# 4_SIM.net
KiCad netlist of a schematic drawn in Altium Designer
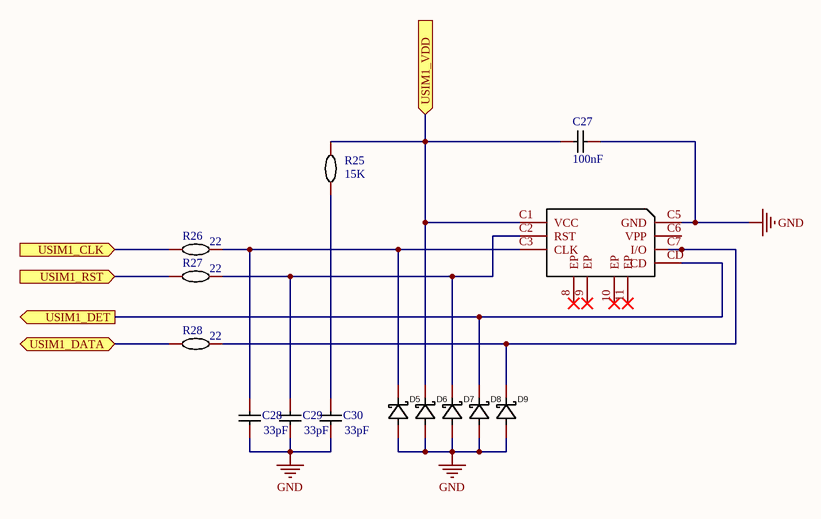
[diagram p0: 4_SIM卡座电路.SchDoc]

(export (version "E")
  (design (tool "Eeschema 10.0.6"))
  (components
    (comp (ref "C27")
      (value "100nF")
      (footprint "0603C")
      (fields (field (name "MANUFACTURER PART") "CL31A106KBHNNNE"))
      (libsource (lib "3_C5157152_TP5000移动电源方案验证板.schdoc") (part "CL31A106KBHNNNE"))
    )
    (comp (ref "C28")
      (value "33pF")
      (footprint "0402C")
      (fields (field (name "MANUFACTURER PART") "CL31A106KBHNNNE"))
      (libsource (lib "3_C5157152_TP5000移动电源方案验证板.schdoc") (part "CL31A106KBHNNNE"))
    )
    (comp (ref "C29")
      (value "33pF")
      (footprint "0402C")
      (fields (field (name "MANUFACTURER PART") "CL31A106KBHNNNE"))
      (libsource (lib "3_C5157152_TP5000移动电源方案验证板.schdoc") (part "CL31A106KBHNNNE"))
    )
    (comp (ref "C30")
      (value "33pF")
      (footprint "0402C")
      (fields (field (name "MANUFACTURER PART") "CL31A106KBHNNNE"))
      (libsource (lib "3_C5157152_TP5000移动电源方案验证板.schdoc") (part "CL31A106KBHNNNE"))
    )
    (comp (ref "CARD1")
      (value "SMN-303")
      (footprint "SIM-SMD_SMN-303")
      (libsource (lib "SIM-3031_SMN-303.schdoc") (part "SMN-303"))
    )
    (comp (ref "D5")
      (value "~")
      (footprint "SOD-123FL_L2.8-W1.8-LS3.7-RD")
      (fields (field (name "MANUFACTURER PART") "SMF75A"))
      (libsource (lib "SMF75A_C51164161_SMF75A_C5116416.schdoc") (part "SMF75A_C5116416"))
    )
    (comp (ref "D6")
      (value "~")
      (footprint "SOD-123FL_L2.8-W1.8-LS3.7-RD")
      (fields (field (name "MANUFACTURER PART") "SMF75A"))
      (libsource (lib "SMF75A_C51164161_SMF75A_C5116416.schdoc") (part "SMF75A_C5116416"))
    )
    (comp (ref "D7")
      (value "~")
      (footprint "SOD-123FL_L2.8-W1.8-LS3.7-RD")
      (fields (field (name "MANUFACTURER PART") "SMF75A"))
      (libsource (lib "SMF75A_C51164161_SMF75A_C5116416.schdoc") (part "SMF75A_C5116416"))
    )
    (comp (ref "D8")
      (value "~")
      (footprint "SOD-123FL_L2.8-W1.8-LS3.7-RD")
      (fields (field (name "MANUFACTURER PART") "SMF75A"))
      (libsource (lib "SMF75A_C51164161_SMF75A_C5116416.schdoc") (part "SMF75A_C5116416"))
    )
    (comp (ref "D9")
      (value "~")
      (footprint "SOD-123FL_L2.8-W1.8-LS3.7-RD")
      (fields (field (name "MANUFACTURER PART") "SMF75A"))
      (libsource (lib "SMF75A_C51164161_SMF75A_C5116416.schdoc") (part "SMF75A_C5116416"))
    )
    (comp (ref "R25")
      (value "4.7K")
      (footprint "0603R")
      (fields
        (field (name "MANUFACTURER") "Tyohm")
        (field (name "MANUFACTURER PART") "RMC06034.7k5%N")
        (field (name "NAME") "15K")
      )
      (libsource (lib "3_C5157152_TP5000移动电源方案验证板.schdoc") (part "RMC06034.7k5%N"))
    )
    (comp (ref "R26") (value "22") (footprint "0402R") (libsource (lib "2_传感器.schdoc") (part "Res_0402")))
    (comp (ref "R27") (value "22") (footprint "0402R") (libsource (lib "2_传感器.schdoc") (part "Res_0402")))
    (comp (ref "R28") (value "22") (footprint "0402R") (libsource (lib "2_传感器.schdoc") (part "Res_0402")))
  )
  (nets
    (net (code "1") (name "/USIM1_CLK") (class "Default")
      (node (ref "R26") (pin "1") (pinfunction "1_1") (pintype "passive"))
    )
    (net (code "2") (name "/USIM1_DATA") (class "Default")
      (node (ref "R28") (pin "1") (pinfunction "1_1") (pintype "passive"))
    )
    (net (code "3") (name "/USIM1_DET") (class "Default")
      (node (ref "CARD1") (pin "CD") (pinfunction "CD_CD") (pintype "passive"))
      (node (ref "D8") (pin "1") (pinfunction "K_1") (pintype "passive"))
    )
    (net (code "4") (name "/USIM1_RST") (class "Default")
      (node (ref "R27") (pin "1") (pinfunction "1_1") (pintype "passive"))
    )
    (net (code "5") (name "/USIM1_VDD") (class "Default")
      (node (ref "C27") (pin "2") (pinfunction "2_2") (pintype "passive"))
      (node (ref "CARD1") (pin "C1") (pinfunction "VCC_C1") (pintype "passive"))
      (node (ref "D6") (pin "1") (pinfunction "K_1") (pintype "passive"))
      (node (ref "R25") (pin "2") (pinfunction "2_2") (pintype "passive"))
    )
    (net (code "6") (name "GND") (class "Default")
      (node (ref "C27") (pin "1") (pinfunction "1_1") (pintype "passive"))
      (node (ref "C28") (pin "1") (pinfunction "1_1") (pintype "passive"))
      (node (ref "C29") (pin "1") (pinfunction "1_1") (pintype "passive"))
      (node (ref "C30") (pin "1") (pinfunction "1_1") (pintype "passive"))
      (node (ref "CARD1") (pin "C5") (pinfunction "GND_C5") (pintype "passive"))
      (node (ref "D5") (pin "2") (pinfunction "A_2") (pintype "passive"))
      (node (ref "D6") (pin "2") (pinfunction "A_2") (pintype "passive"))
      (node (ref "D7") (pin "2") (pinfunction "A_2") (pintype "passive"))
      (node (ref "D8") (pin "2") (pinfunction "A_2") (pintype "passive"))
      (node (ref "D9") (pin "2") (pinfunction "A_2") (pintype "passive"))
    )
    (net (code "7") (name "Net-(C30-Pad2)") (class "Default")
      (node (ref "C30") (pin "2") (pinfunction "2_2") (pintype "passive"))
      (node (ref "R25") (pin "1") (pinfunction "1_1") (pintype "passive"))
    )
    (net (code "8") (name "Net-(CARD1-CLK)") (class "Default")
      (node (ref "C28") (pin "2") (pinfunction "2_2") (pintype "passive"))
      (node (ref "CARD1") (pin "C3") (pinfunction "CLK_C3") (pintype "passive"))
      (node (ref "D5") (pin "1") (pinfunction "K_1") (pintype "passive"))
      (node (ref "R26") (pin "2") (pinfunction "2_2") (pintype "passive"))
    )
    (net (code "9") (name "Net-(CARD1-I{slash}O)") (class "Default")
      (node (ref "CARD1") (pin "C7") (pinfunction "I/O_C7") (pintype "passive"))
      (node (ref "D9") (pin "1") (pinfunction "K_1") (pintype "passive"))
      (node (ref "R28") (pin "2") (pinfunction "2_2") (pintype "passive"))
    )
    (net (code "10") (name "Net-(CARD1-RST)") (class "Default")
      (node (ref "C29") (pin "2") (pinfunction "2_2") (pintype "passive"))
      (node (ref "CARD1") (pin "C2") (pinfunction "RST_C2") (pintype "passive"))
      (node (ref "D7") (pin "1") (pinfunction "K_1") (pintype "passive"))
      (node (ref "R27") (pin "2") (pinfunction "2_2") (pintype "passive"))
    )
    (net (code "11") (name "unconnected-(CARD1-EP-Pad8)") (class "Default")
      (node (ref "CARD1") (pin "8") (pinfunction "EP_8") (pintype "passive+no_connect"))
    )
    (net (code "12") (name "unconnected-(CARD1-EP-Pad9)") (class "Default")
      (node (ref "CARD1") (pin "9") (pinfunction "EP_9") (pintype "passive+no_connect"))
    )
    (net (code "13") (name "unconnected-(CARD1-EP-Pad10)") (class "Default")
      (node (ref "CARD1") (pin "10") (pinfunction "EP_10") (pintype "passive+no_connect"))
    )
    (net (code "14") (name "unconnected-(CARD1-EP-Pad11)") (class "Default")
      (node (ref "CARD1") (pin "11") (pinfunction "EP_11") (pintype "passive+no_connect"))
    )
    (net (code "15") (name "unconnected-(CARD1-VPP-PadC6)") (class "Default")
      (node (ref "CARD1") (pin "C6") (pinfunction "VPP_C6") (pintype "passive"))
    )
  )
)
